# main.net
KiCad netlist of a schematic drawn in Altium Designer
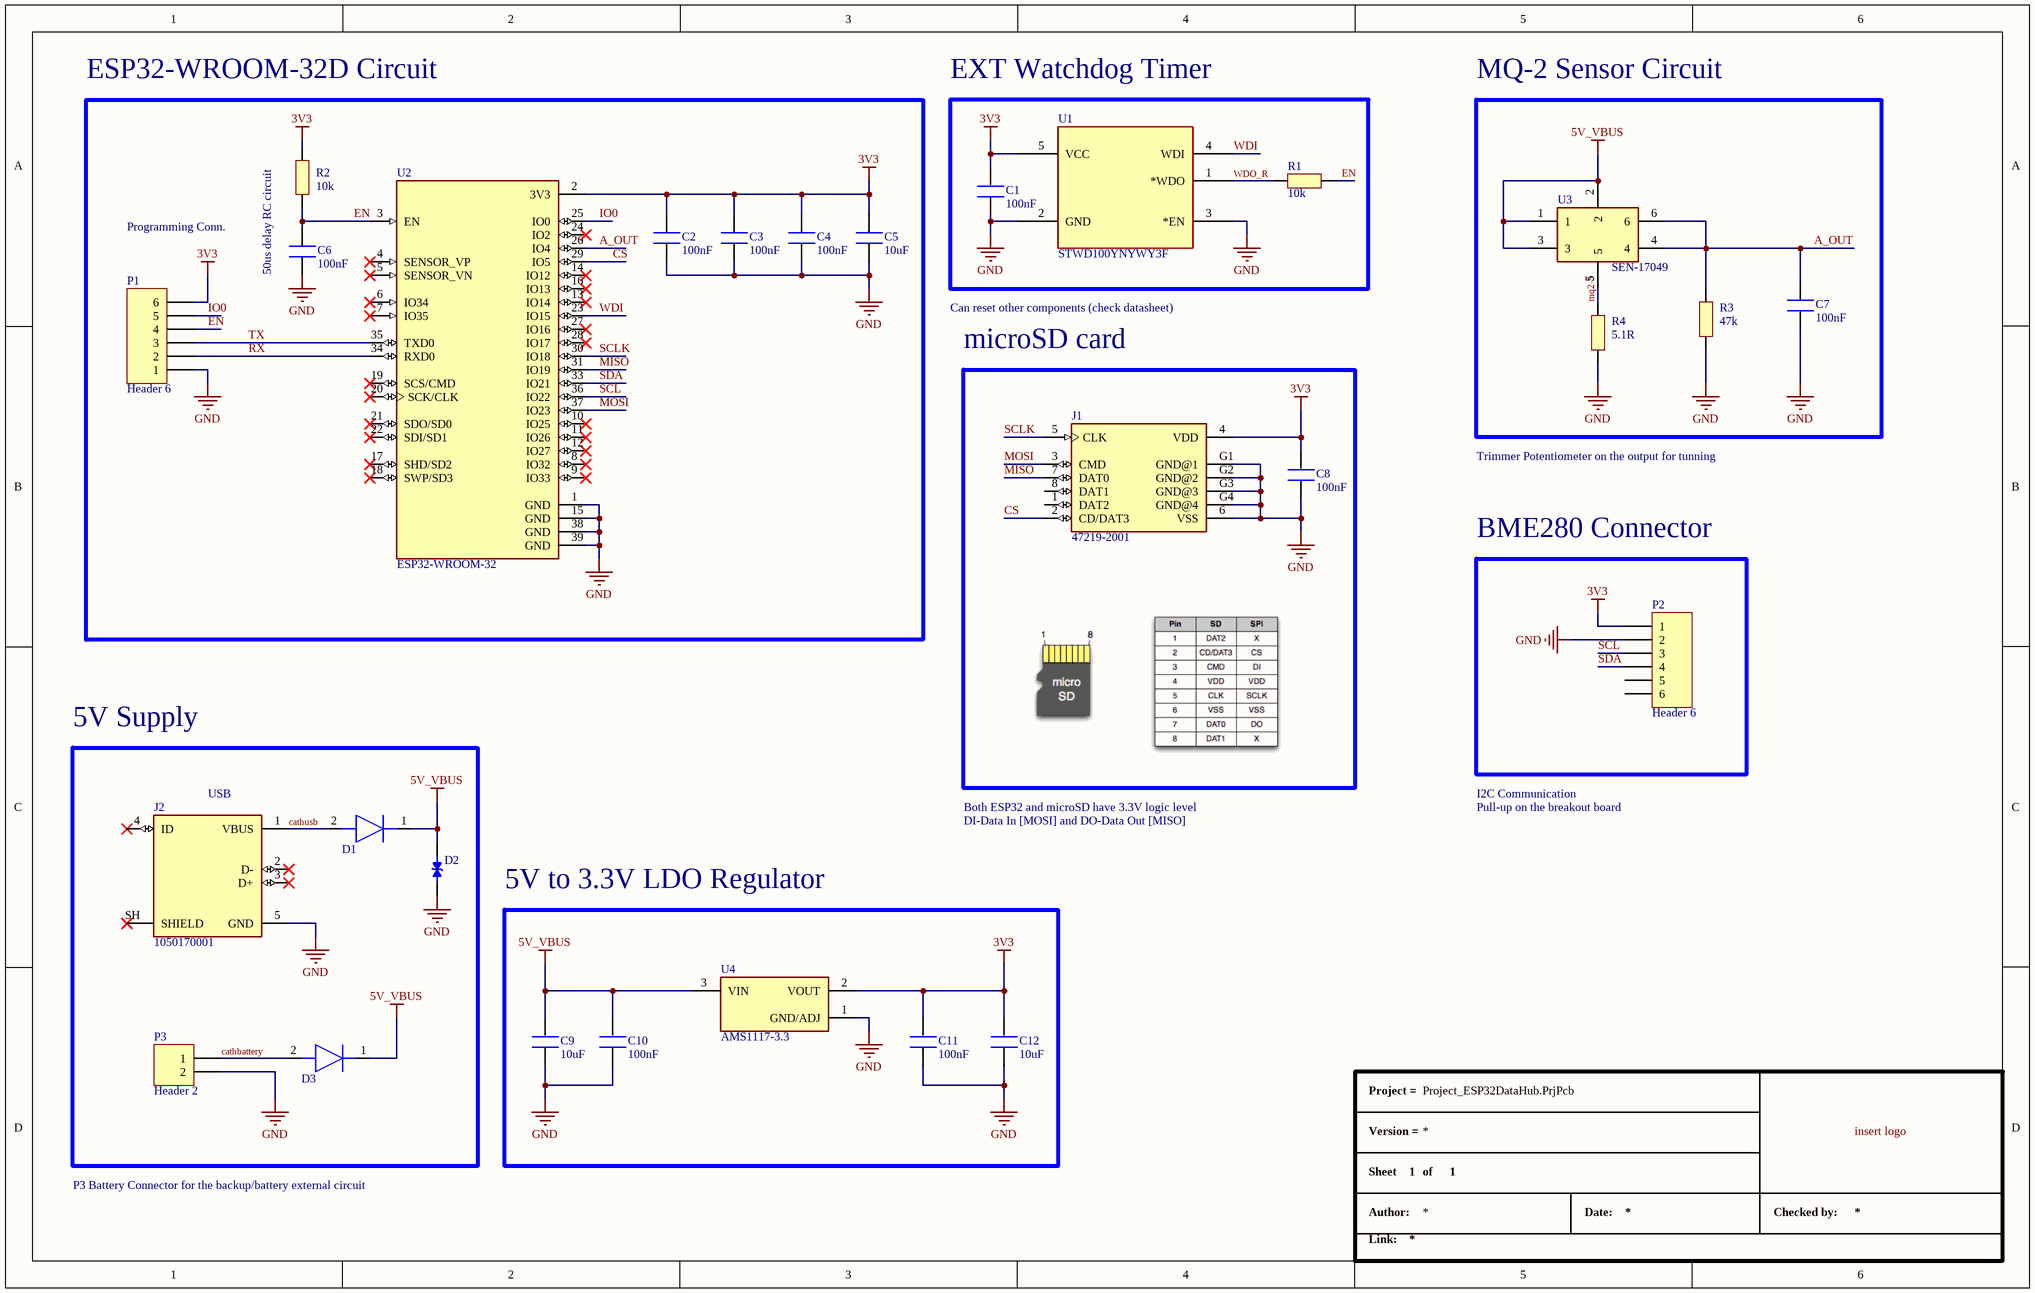
[diagram p0: main.SchDoc]

(export (version "E")
  (design (tool "Eeschema 10.0.6"))
  (components
    (comp (ref "C1")
      (value "100nF")
      (footprint "CAP_0603")
      (description "Capacitor SMD 0603 Generic")
      (libsource (lib "GenericCompLib") (part "Cap_0603"))
    )
    (comp (ref "C2")
      (value "100nF")
      (footprint "CAP_0603")
      (description "Capacitor SMD 0603 Generic")
      (libsource (lib "GenericCompLib") (part "Cap_0603"))
    )
    (comp (ref "C3")
      (value "100nF")
      (footprint "CAP_0603")
      (description "Capacitor SMD 0603 Generic")
      (libsource (lib "GenericCompLib") (part "Cap_0603"))
    )
    (comp (ref "C4")
      (value "100nF")
      (footprint "CAP_0603")
      (description "Capacitor SMD 0603 Generic")
      (libsource (lib "GenericCompLib") (part "Cap_0603"))
    )
    (comp (ref "C5")
      (value "10uF")
      (footprint "CAP_0603")
      (description "Capacitor SMD 0603 Generic")
      (libsource (lib "GenericCompLib") (part "Cap_0603"))
    )
    (comp (ref "C6")
      (value "100nF")
      (footprint "CAP_0603")
      (description "Capacitor SMD 0603 Generic")
      (libsource (lib "GenericCompLib") (part "Cap_0603"))
    )
    (comp (ref "C7")
      (value "100nF")
      (footprint "CAP_0603")
      (description "Capacitor SMD 0603 Generic")
      (libsource (lib "GenericCompLib") (part "Cap_0603"))
    )
    (comp (ref "C8")
      (value "100nF")
      (footprint "CAP_0603")
      (description "Capacitor SMD 0603 Generic")
      (libsource (lib "GenericCompLib") (part "Cap_0603"))
    )
    (comp (ref "C9")
      (value "10uF")
      (footprint "CAP_0603")
      (description "Capacitor SMD 0603 Generic")
      (libsource (lib "GenericCompLib") (part "Cap_0603"))
    )
    (comp (ref "C10")
      (value "100nF")
      (footprint "CAP_0603")
      (description "Capacitor SMD 0603 Generic")
      (libsource (lib "GenericCompLib") (part "Cap_0603"))
    )
    (comp (ref "C11")
      (value "100nF")
      (footprint "CAP_0603")
      (description "Capacitor SMD 0603 Generic")
      (libsource (lib "GenericCompLib") (part "Cap_0603"))
    )
    (comp (ref "C12")
      (value "10uF")
      (footprint "CAP_0603")
      (description "Capacitor SMD 0603 Generic")
      (libsource (lib "GenericCompLib") (part "Cap_0603"))
    )
    (comp (ref "D1")
      (value "CDBA240LL-HF")
      (footprint "SamacSys:DIOM5225X250N")
      (description "Diode")
      (fields (field (name "MOUSER PART NUMBER") "750-CDBA240LL-HF"))
      (libsource (lib "*") (part "CDBA240LL-HF"))
    )
    (comp (ref "D2")
      (value "SLESDL0603-12")
      (footprint "TVS0603")
      (libsource (lib "GenericCompLib") (part "TVSDiode0603"))
    )
    (comp (ref "D3")
      (value "CDBA240LL-HF")
      (footprint "SamacSys:DIOM5225X250N")
      (description "Diode")
      (fields (field (name "MOUSER PART NUMBER") "750-CDBA240LL-HF"))
      (libsource (lib "*") (part "CDBA240LL-HF"))
    )
    (comp (ref "J1")
      (value "47219-2001")
      (footprint "47219-2001")
      (description "1.1mm Pitch microSD Card Connector, Hinge Type, Lead Free ¦ Molex Incorporated 47219-2001")
      (libsource (lib "ConnLib") (part "microSD Card Conn"))
    )
    (comp (ref "J2")
      (value "1050170001")
      (footprint "MOLEX-1050170001")
      (description "USB - micro B USB 2.0 Receptacle Connector 5 Position Surface Mount, Right Angle; Through Hole")
      (libsource (lib "ConnLib") (part "Molex_1050170001"))
    )
    (comp (ref "P1")
      (value "Header 6")
      (footprint "HDR1X6")
      (description "Header, 6-Pin")
      (fields (field (name "PUBLISHER") "Altium Limited"))
      (libsource (lib "") (part "Header 6_1"))
    )
    (comp (ref "P2")
      (value "Header 6")
      (footprint "HDR1X6")
      (description "Header, 6-Pin")
      (fields (field (name "PUBLISHER") "Altium Limited"))
      (libsource (lib "Miscellaneous Connectors") (part "Header 6"))
    )
    (comp (ref "P3")
      (value "Header 2")
      (footprint "HDR1X2")
      (description "Header, 2-Pin")
      (fields (field (name "PUBLISHER") "Altium Limited"))
      (libsource (lib "Miscellaneous Connectors") (part "Header 2"))
    )
    (comp (ref "R1")
      (value "10k")
      (footprint "RES_0603")
      (description "Resistor SMD 0603 Generic")
      (libsource (lib "") (part "Res_0603_1"))
    )
    (comp (ref "R2")
      (value "10k")
      (footprint "RES_0603")
      (description "Resistor SMD 0603 Generic")
      (libsource (lib "GenericCompLib") (part "Res_0603"))
    )
    (comp (ref "R3")
      (value "47k")
      (footprint "RES_0603")
      (description "Resistor SMD 0603 Generic")
      (libsource (lib "GenericCompLib") (part "Res_0603"))
    )
    (comp (ref "R4")
      (value "5.1R")
      (footprint "RES_0603")
      (description "Resistor SMD 0603 Generic")
      (libsource (lib "GenericCompLib") (part "Res_0603"))
    )
    (comp (ref "U1")
      (value "STWD100YNYWY3F")
      (footprint "STWD100YNYWY3F")
      (description "1.12s Active Low 1 SOT-23-5 Monitors & Reset Circuits ROHS")
      (libsource (lib "ICLib") (part "STWD100YNYWY3F"))
    )
    (comp (ref "U2")
      (value "ESP32-WROOM-32")
      (footprint "ESP32-WROOM-32-Nx")
      (libsource (lib "ICLib") (part "ESP32-WROOM-32-Nx"))
    )
    (comp (ref "U3")
      (value "SEN-17049")
      (footprint "SEN17049")
      (description "Undefined or Miscellaneous")
      (fields (field (name "MOUSER PART NUMBER") "474-SEN-17049"))
      (libsource (lib "SamacSys") (part "SEN-17049"))
    )
    (comp (ref "U4")
      (value "AMS1117-3.3")
      (footprint "SOT229P700X180-4N")
      (description "Sot223/Pkg 1-Amp 3.3-Volt Low Drop Out Voltage Regulatator")
      (libsource (lib "PowerSupplyICLib") (part "AMS1117-3.3"))
    )
  )
  (nets
    (net (code "1") (name "/A_OUT") (class "Default")
      (node (ref "C7") (pin "2") (pinfunction "2_2") (pintype "passive"))
      (node (ref "R3") (pin "2") (pinfunction "2_2") (pintype "passive"))
      (node (ref "U2") (pin "26") (pinfunction "IO4_26") (pintype "bidirectional"))
      (node (ref "U3") (pin "4") (pinfunction "4_4") (pintype "passive"))
      (node (ref "U3") (pin "6") (pinfunction "6_6") (pintype "passive"))
    )
    (net (code "2") (name "/CS") (class "Default")
      (node (ref "J1") (pin "2") (pinfunction "CD/DAT3_2") (pintype "bidirectional"))
      (node (ref "U2") (pin "29") (pinfunction "IO5_29") (pintype "bidirectional"))
    )
    (net (code "3") (name "/EN") (class "Default")
      (node (ref "C6") (pin "2") (pinfunction "2_2") (pintype "passive"))
      (node (ref "P1") (pin "4") (pinfunction "4_4") (pintype "passive"))
      (node (ref "R1") (pin "2") (pinfunction "2_2") (pintype "passive"))
      (node (ref "R2") (pin "1") (pinfunction "1_1") (pintype "passive"))
      (node (ref "U2") (pin "3") (pinfunction "EN_3") (pintype "input"))
    )
    (net (code "4") (name "/IO0") (class "Default")
      (node (ref "P1") (pin "5") (pinfunction "5_5") (pintype "passive"))
      (node (ref "U2") (pin "25") (pinfunction "IO0_25") (pintype "bidirectional"))
    )
    (net (code "5") (name "/MISO") (class "Default")
      (node (ref "J1") (pin "7") (pinfunction "DAT0_7") (pintype "bidirectional"))
      (node (ref "U2") (pin "31") (pinfunction "IO19_31") (pintype "bidirectional"))
    )
    (net (code "6") (name "/MOSI") (class "Default")
      (node (ref "J1") (pin "3") (pinfunction "CMD_3") (pintype "bidirectional"))
      (node (ref "U2") (pin "37") (pinfunction "IO23_37") (pintype "bidirectional"))
    )
    (net (code "7") (name "/RX") (class "Default")
      (node (ref "P1") (pin "2") (pinfunction "2_2") (pintype "passive"))
      (node (ref "U2") (pin "34") (pinfunction "RXD0_34") (pintype "bidirectional"))
    )
    (net (code "8") (name "/SCL") (class "Default")
      (node (ref "P2") (pin "3") (pinfunction "3_3") (pintype "passive"))
      (node (ref "U2") (pin "36") (pinfunction "IO22_36") (pintype "bidirectional"))
    )
    (net (code "9") (name "/SCLK") (class "Default")
      (node (ref "J1") (pin "5") (pinfunction "CLK_5") (pintype "input"))
      (node (ref "U2") (pin "30") (pinfunction "IO18_30") (pintype "bidirectional"))
    )
    (net (code "10") (name "/SDA") (class "Default")
      (node (ref "P2") (pin "4") (pinfunction "4_4") (pintype "passive"))
      (node (ref "U2") (pin "33") (pinfunction "IO21_33") (pintype "bidirectional"))
    )
    (net (code "11") (name "/TX") (class "Default")
      (node (ref "P1") (pin "3") (pinfunction "3_3") (pintype "passive"))
      (node (ref "U2") (pin "35") (pinfunction "TXD0_35") (pintype "bidirectional"))
    )
    (net (code "12") (name "/WDI") (class "Default")
      (node (ref "U1") (pin "4") (pinfunction "WDI_4") (pintype "passive"))
      (node (ref "U2") (pin "23") (pinfunction "IO15_23") (pintype "bidirectional"))
    )
    (net (code "13") (name "/WDO_R") (class "Default")
      (node (ref "R1") (pin "1") (pinfunction "1_1") (pintype "passive"))
      (node (ref "U1") (pin "1") (pinfunction "*WDO_1") (pintype "passive"))
    )
    (net (code "14") (name "/cathbattery") (class "Default")
      (node (ref "D3") (pin "2") (pinfunction "A_2") (pintype "passive"))
      (node (ref "P3") (pin "1") (pinfunction "1_1") (pintype "passive"))
    )
    (net (code "15") (name "/cathusb") (class "Default")
      (node (ref "D1") (pin "2") (pinfunction "A_2") (pintype "passive"))
      (node (ref "J2") (pin "1") (pinfunction "VBUS_1") (pintype "power_in"))
    )
    (net (code "17") (name "/mq2-5") (class "Default")
      (node (ref "R4") (pin "2") (pinfunction "2_2") (pintype "passive"))
      (node (ref "U3") (pin "5") (pinfunction "5_5") (pintype "passive"))
    )
    (net (code "18") (name "3V3") (class "Default")
      (node (ref "C1") (pin "1") (pinfunction "1_1") (pintype "passive"))
      (node (ref "C11") (pin "2") (pinfunction "2_2") (pintype "passive"))
      (node (ref "C12") (pin "2") (pinfunction "2_2") (pintype "passive"))
      (node (ref "C2") (pin "2") (pinfunction "2_2") (pintype "passive"))
      (node (ref "C3") (pin "2") (pinfunction "2_2") (pintype "passive"))
      (node (ref "C4") (pin "2") (pinfunction "2_2") (pintype "passive"))
      (node (ref "C5") (pin "2") (pinfunction "2_2") (pintype "passive"))
      (node (ref "C8") (pin "1") (pinfunction "1_1") (pintype "passive"))
      (node (ref "J1") (pin "4") (pinfunction "VDD_4") (pintype "power_in"))
      (node (ref "P1") (pin "6") (pinfunction "6_6") (pintype "passive"))
      (node (ref "P2") (pin "1") (pinfunction "1_1") (pintype "passive"))
      (node (ref "R2") (pin "2") (pinfunction "2_2") (pintype "passive"))
      (node (ref "U1") (pin "5") (pinfunction "VCC_5") (pintype "power_in"))
      (node (ref "U2") (pin "2") (pinfunction "3V3_2") (pintype "power_in"))
      (node (ref "U4") (pin "2") (pinfunction "VOUT_2") (pintype "power_in"))
    )
    (net (code "19") (name "5V_VBUS") (class "Default")
      (node (ref "C10") (pin "2") (pinfunction "2_2") (pintype "passive"))
      (node (ref "C9") (pin "2") (pinfunction "2_2") (pintype "passive"))
      (node (ref "D1") (pin "1") (pinfunction "K_1") (pintype "passive"))
      (node (ref "D2") (pin "2") (pinfunction "2_2") (pintype "passive"))
      (node (ref "D3") (pin "1") (pinfunction "K_1") (pintype "passive"))
      (node (ref "U3") (pin "1") (pinfunction "1_1") (pintype "passive"))
      (node (ref "U3") (pin "2") (pinfunction "2_2") (pintype "passive"))
      (node (ref "U3") (pin "3") (pinfunction "3_3") (pintype "passive"))
      (node (ref "U4") (pin "3") (pinfunction "VIN_3") (pintype "power_in"))
    )
    (net (code "20") (name "GND") (class "Default")
      (node (ref "C1") (pin "2") (pinfunction "2_2") (pintype "passive"))
      (node (ref "C10") (pin "1") (pinfunction "1_1") (pintype "passive"))
      (node (ref "C11") (pin "1") (pinfunction "1_1") (pintype "passive"))
      (node (ref "C12") (pin "1") (pinfunction "1_1") (pintype "passive"))
      (node (ref "C2") (pin "1") (pinfunction "1_1") (pintype "passive"))
      (node (ref "C3") (pin "1") (pinfunction "1_1") (pintype "passive"))
      (node (ref "C4") (pin "1") (pinfunction "1_1") (pintype "passive"))
      (node (ref "C5") (pin "1") (pinfunction "1_1") (pintype "passive"))
      (node (ref "C6") (pin "1") (pinfunction "1_1") (pintype "passive"))
      (node (ref "C7") (pin "1") (pinfunction "1_1") (pintype "passive"))
      (node (ref "C8") (pin "2") (pinfunction "2_2") (pintype "passive"))
      (node (ref "C9") (pin "1") (pinfunction "1_1") (pintype "passive"))
      (node (ref "D2") (pin "1") (pinfunction "1_1") (pintype "passive"))
      (node (ref "J1") (pin "6") (pinfunction "VSS_6") (pintype "power_in"))
      (node (ref "J1") (pin "G1") (pinfunction "GND@1_G1") (pintype "power_in"))
      (node (ref "J1") (pin "G2") (pinfunction "GND@2_G2") (pintype "power_in"))
      (node (ref "J1") (pin "G3") (pinfunction "GND@3_G3") (pintype "power_in"))
      (node (ref "J1") (pin "G4") (pinfunction "GND@4_G4") (pintype "power_in"))
      (node (ref "J2") (pin "5") (pinfunction "GND_5") (pintype "power_in"))
      (node (ref "P1") (pin "1") (pinfunction "1_1") (pintype "passive"))
      (node (ref "P2") (pin "2") (pinfunction "2_2") (pintype "passive"))
      (node (ref "P3") (pin "2") (pinfunction "2_2") (pintype "passive"))
      (node (ref "R3") (pin "1") (pinfunction "1_1") (pintype "passive"))
      (node (ref "R4") (pin "1") (pinfunction "1_1") (pintype "passive"))
      (node (ref "U1") (pin "2") (pinfunction "GND_2") (pintype "power_in"))
      (node (ref "U1") (pin "3") (pinfunction "*EN_3") (pintype "passive"))
      (node (ref "U2") (pin "1") (pinfunction "GND_1") (pintype "power_in"))
      (node (ref "U2") (pin "15") (pinfunction "GND_15") (pintype "power_in"))
      (node (ref "U2") (pin "38") (pinfunction "GND_38") (pintype "power_in"))
      (node (ref "U2") (pin "39") (pinfunction "GND_39") (pintype "power_in"))
      (node (ref "U4") (pin "1") (pinfunction "GND/ADJ_1") (pintype "power_in"))
    )
    (net (code "21") (name "unconnected-(J1-DAT1-Pad8)") (class "Default")
      (node (ref "J1") (pin "8") (pinfunction "DAT1_8") (pintype "bidirectional"))
    )
    (net (code "22") (name "unconnected-(J1-DAT2-Pad1)") (class "Default")
      (node (ref "J1") (pin "1") (pinfunction "DAT2_1") (pintype "bidirectional"))
    )
    (net (code "23") (name "unconnected-(J2-D+-Pad3)") (class "Default")
      (node (ref "J2") (pin "3") (pinfunction "D+_3") (pintype "bidirectional+no_connect"))
    )
    (net (code "24") (name "unconnected-(J2-D--Pad2)") (class "Default")
      (node (ref "J2") (pin "2") (pinfunction "D-_2") (pintype "bidirectional+no_connect"))
    )
    (net (code "25") (name "unconnected-(J2-ID-Pad4)") (class "Default")
      (node (ref "J2") (pin "4") (pinfunction "ID_4") (pintype "bidirectional+no_connect"))
    )
    (net (code "26") (name "unconnected-(J2-SHIELD-PadSH)") (class "Default")
      (node (ref "J2") (pin "SH") (pinfunction "SHIELD_SH") (pintype "passive+no_connect"))
    )
    (net (code "27") (name "unconnected-(P2-Pad5)") (class "Default")
      (node (ref "P2") (pin "5") (pinfunction "5_5") (pintype "passive"))
    )
    (net (code "28") (name "unconnected-(P2-Pad6)") (class "Default")
      (node (ref "P2") (pin "6") (pinfunction "6_6") (pintype "passive"))
    )
    (net (code "29") (name "unconnected-(U2-IO2-Pad24)") (class "Default")
      (node (ref "U2") (pin "24") (pinfunction "IO2_24") (pintype "bidirectional+no_connect"))
    )
    (net (code "30") (name "unconnected-(U2-IO12-Pad14)") (class "Default")
      (node (ref "U2") (pin "14") (pinfunction "IO12_14") (pintype "bidirectional+no_connect"))
    )
    (net (code "31") (name "unconnected-(U2-IO13-Pad16)") (class "Default")
      (node (ref "U2") (pin "16") (pinfunction "IO13_16") (pintype "bidirectional+no_connect"))
    )
    (net (code "32") (name "unconnected-(U2-IO14-Pad13)") (class "Default")
      (node (ref "U2") (pin "13") (pinfunction "IO14_13") (pintype "bidirectional+no_connect"))
    )
    (net (code "33") (name "unconnected-(U2-IO16-Pad27)") (class "Default")
      (node (ref "U2") (pin "27") (pinfunction "IO16_27") (pintype "bidirectional+no_connect"))
    )
    (net (code "34") (name "unconnected-(U2-IO17-Pad28)") (class "Default")
      (node (ref "U2") (pin "28") (pinfunction "IO17_28") (pintype "bidirectional+no_connect"))
    )
    (net (code "35") (name "unconnected-(U2-IO25-Pad10)") (class "Default")
      (node (ref "U2") (pin "10") (pinfunction "IO25_10") (pintype "bidirectional+no_connect"))
    )
    (net (code "36") (name "unconnected-(U2-IO26-Pad11)") (class "Default")
      (node (ref "U2") (pin "11") (pinfunction "IO26_11") (pintype "bidirectional+no_connect"))
    )
    (net (code "37") (name "unconnected-(U2-IO27-Pad12)") (class "Default")
      (node (ref "U2") (pin "12") (pinfunction "IO27_12") (pintype "bidirectional+no_connect"))
    )
    (net (code "38") (name "unconnected-(U2-IO32-Pad8)") (class "Default")
      (node (ref "U2") (pin "8") (pinfunction "IO32_8") (pintype "bidirectional+no_connect"))
    )
    (net (code "39") (name "unconnected-(U2-IO33-Pad9)") (class "Default")
      (node (ref "U2") (pin "9") (pinfunction "IO33_9") (pintype "bidirectional+no_connect"))
    )
    (net (code "40") (name "unconnected-(U2-IO34-Pad6)") (class "Default")
      (node (ref "U2") (pin "6") (pinfunction "IO34_6") (pintype "input+no_connect"))
    )
    (net (code "41") (name "unconnected-(U2-IO35-Pad7)") (class "Default")
      (node (ref "U2") (pin "7") (pinfunction "IO35_7") (pintype "input+no_connect"))
    )
    (net (code "42") (name "unconnected-(U2-SCK{slash}CLK-Pad20)") (class "Default")
      (node (ref "U2") (pin "20") (pinfunction "SCK/CLK_20") (pintype "bidirectional+no_connect"))
    )
    (net (code "43") (name "unconnected-(U2-SCS{slash}CMD-Pad19)") (class "Default")
      (node (ref "U2") (pin "19") (pinfunction "SCS/CMD_19") (pintype "bidirectional+no_connect"))
    )
    (net (code "44") (name "unconnected-(U2-SDI{slash}SD1-Pad22)") (class "Default")
      (node (ref "U2") (pin "22") (pinfunction "SDI/SD1_22") (pintype "bidirectional+no_connect"))
    )
    (net (code "45") (name "unconnected-(U2-SDO{slash}SD0-Pad21)") (class "Default")
      (node (ref "U2") (pin "21") (pinfunction "SDO/SD0_21") (pintype "bidirectional+no_connect"))
    )
    (net (code "46") (name "unconnected-(U2-SENSOR_VN-Pad5)") (class "Default")
      (node (ref "U2") (pin "5") (pinfunction "SENSOR_VN_5") (pintype "input+no_connect"))
    )
    (net (code "47") (name "unconnected-(U2-SENSOR_VP-Pad4)") (class "Default")
      (node (ref "U2") (pin "4") (pinfunction "SENSOR_VP_4") (pintype "input+no_connect"))
    )
    (net (code "48") (name "unconnected-(U2-SHD{slash}SD2-Pad17)") (class "Default")
      (node (ref "U2") (pin "17") (pinfunction "SHD/SD2_17") (pintype "bidirectional+no_connect"))
    )
    (net (code "49") (name "unconnected-(U2-SWP{slash}SD3-Pad18)") (class "Default")
      (node (ref "U2") (pin "18") (pinfunction "SWP/SD3_18") (pintype "bidirectional+no_connect"))
    )
  )
)
